# tec_controller.net
KiCad netlist of a schematic drawn in EAGLE
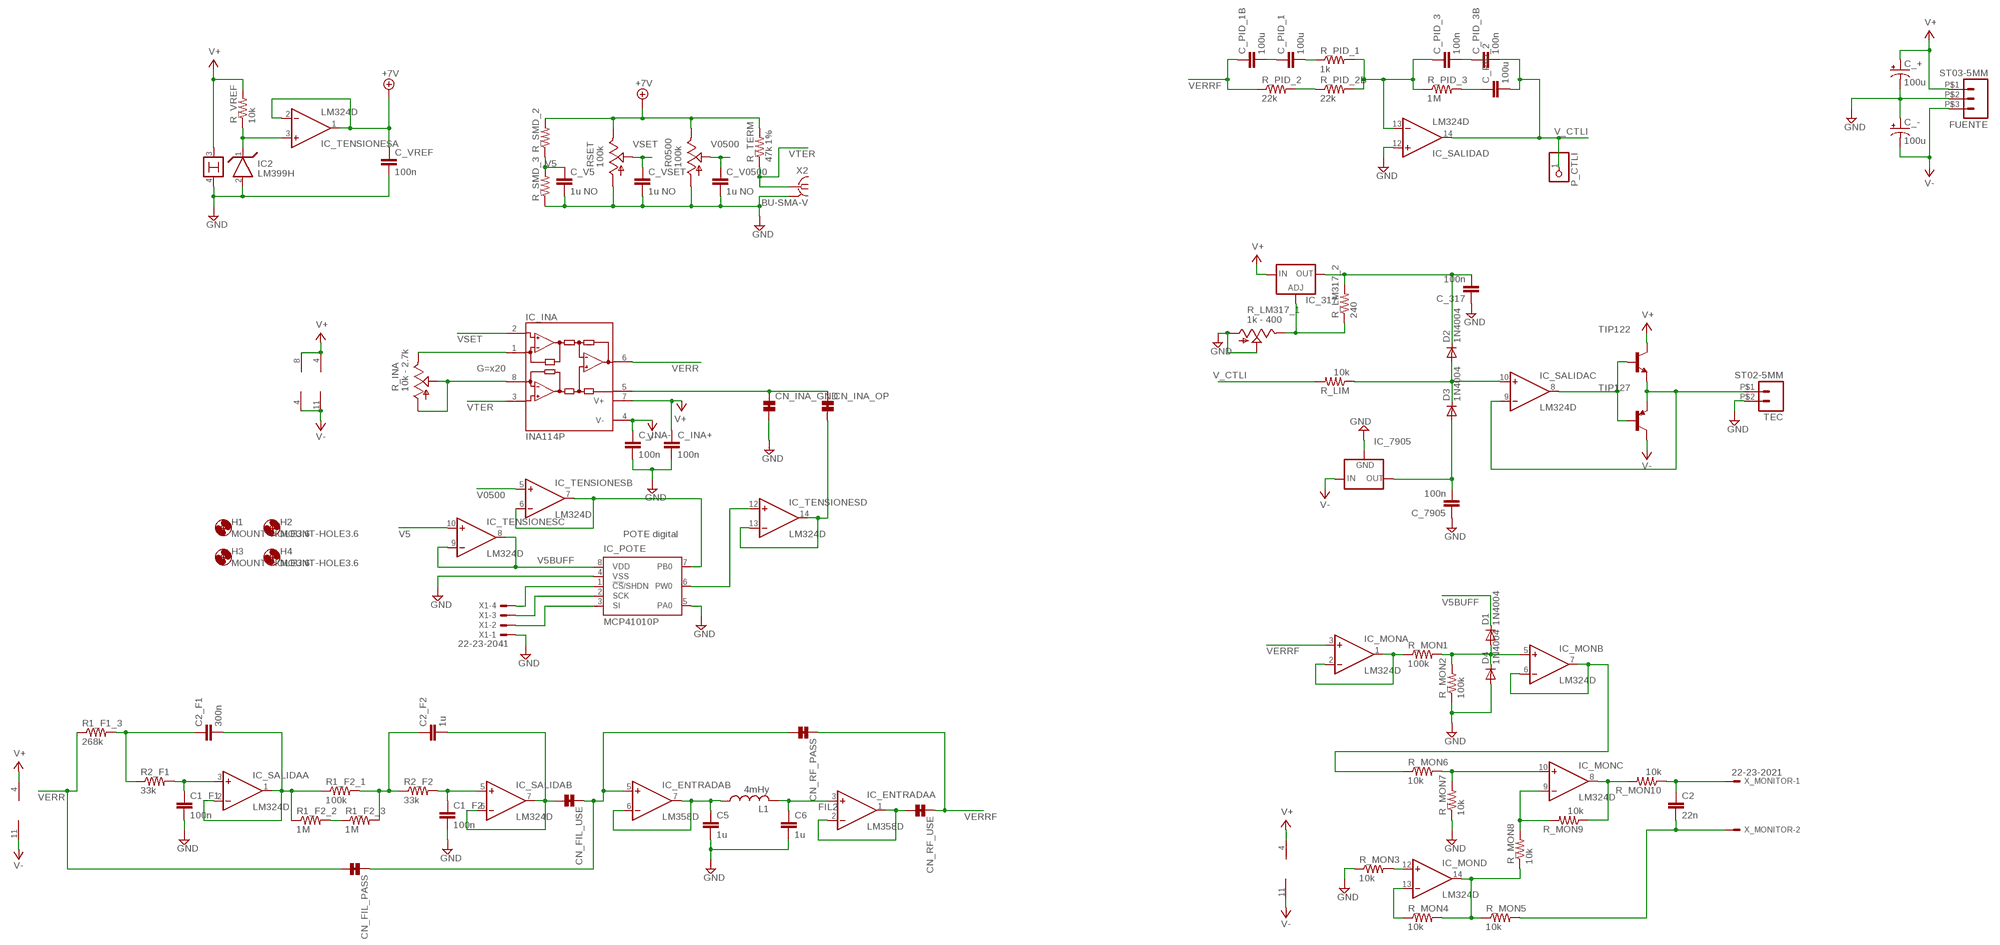
[diagram p0: schematic, sheet 1]

(export (version "E")
  (design (tool "Eeschema 10.0.6"))
  (components
    (comp (ref "C1_F1")
      (value "100n")
      (footprint "eagle-import:C0603")
      (libsource (lib "eagle-import") (part "C-EUC0603"))
    )
    (comp (ref "C1_F2")
      (value "100n")
      (footprint "eagle-import:C0603")
      (libsource (lib "eagle-import") (part "C-EUC0603"))
    )
    (comp (ref "C2")
      (value "22n")
      (footprint "eagle-import:C1206")
      (libsource (lib "eagle-import") (part "C-EUC1206"))
    )
    (comp (ref "C2_F1")
      (value "300n")
      (footprint "eagle-import:C0603")
      (libsource (lib "eagle-import") (part "C-EUC0603"))
    )
    (comp (ref "C2_F2")
      (value "1u")
      (footprint "eagle-import:C0805")
      (libsource (lib "eagle-import") (part "C-EUC0805"))
    )
    (comp (ref "C5")
      (value "1u")
      (footprint "eagle-import:C0805")
      (libsource (lib "eagle-import") (part "C-EUC0805"))
    )
    (comp (ref "C6")
      (value "1u")
      (footprint "eagle-import:C0805")
      (libsource (lib "eagle-import") (part "C-EUC0805"))
    )
    (comp (ref "CN_FIL_PASS")
      (value "LINK")
      (footprint "eagle-import:LINK_PAC_0603")
      (libsource (lib "eagle-import") (part "LINK"))
    )
    (comp (ref "CN_FIL_USE")
      (value "LINK")
      (footprint "eagle-import:LINK_PAC_0603")
      (libsource (lib "eagle-import") (part "LINK"))
    )
    (comp (ref "CN_INA_GND")
      (value "LINK")
      (footprint "eagle-import:LINK_PAC_0603")
      (libsource (lib "eagle-import") (part "LINK"))
    )
    (comp (ref "CN_INA_OP")
      (value "LINK")
      (footprint "eagle-import:LINK_PAC_0603")
      (libsource (lib "eagle-import") (part "LINK"))
    )
    (comp (ref "CN_RF_PASS")
      (value "LINK")
      (footprint "eagle-import:LINK_PAC_0603")
      (libsource (lib "eagle-import") (part "LINK"))
    )
    (comp (ref "CN_RF_USE")
      (value "LINK")
      (footprint "eagle-import:LINK_PAC_0603")
      (libsource (lib "eagle-import") (part "LINK"))
    )
    (comp (ref "C_+")
      (value "100u")
      (footprint "eagle-import:E3,5-10")
      (libsource (lib "eagle-import") (part "CPOL-USE3.5-10"))
    )
    (comp (ref "C_-")
      (value "100u")
      (footprint "eagle-import:E3,5-10")
      (libsource (lib "eagle-import") (part "CPOL-USE3.5-10"))
    )
    (comp (ref "C_317")
      (value "100n")
      (footprint "eagle-import:C0603")
      (libsource (lib "eagle-import") (part "C-EUC0603"))
    )
    (comp (ref "C_7905")
      (value "100n")
      (footprint "eagle-import:C0603")
      (libsource (lib "eagle-import") (part "C-EUC0603"))
    )
    (comp (ref "C_INA+")
      (value "100n")
      (footprint "eagle-import:C0603")
      (libsource (lib "eagle-import") (part "C-EUC0603"))
    )
    (comp (ref "C_INA-")
      (value "100n")
      (footprint "eagle-import:C0603")
      (libsource (lib "eagle-import") (part "C-EUC0603"))
    )
    (comp (ref "C_PID_1")
      (value "100u")
      (footprint "eagle-import:C050-050X075")
      (libsource (lib "eagle-import") (part "C-EU050-050X075"))
    )
    (comp (ref "C_PID_1B")
      (value "100u")
      (footprint "eagle-import:C050-050X075")
      (libsource (lib "eagle-import") (part "C-EU050-050X075"))
    )
    (comp (ref "C_PID_2")
      (value "100u")
      (footprint "eagle-import:C050-050X075")
      (libsource (lib "eagle-import") (part "C-EU050-050X075"))
    )
    (comp (ref "C_PID_3")
      (value "100n")
      (footprint "eagle-import:C0603")
      (libsource (lib "eagle-import") (part "C-EUC0603"))
    )
    (comp (ref "C_PID_3B")
      (value "100n")
      (footprint "eagle-import:C0603")
      (libsource (lib "eagle-import") (part "C-EUC0603"))
    )
    (comp (ref "C_V5")
      (value "1u NO")
      (footprint "eagle-import:C0805")
      (libsource (lib "eagle-import") (part "C-EUC0805"))
    )
    (comp (ref "C_V0500")
      (value "1u NO")
      (footprint "eagle-import:C0805")
      (libsource (lib "eagle-import") (part "C-EUC0805"))
    )
    (comp (ref "C_VREF")
      (value "100n")
      (footprint "eagle-import:C0603")
      (libsource (lib "eagle-import") (part "C-EUC0603"))
    )
    (comp (ref "C_VSET")
      (value "1u NO")
      (footprint "eagle-import:C0805")
      (libsource (lib "eagle-import") (part "C-EUC0805"))
    )
    (comp (ref "D1")
      (value "1N4004")
      (footprint "eagle-import:DO41-10")
      (libsource (lib "eagle-import") (part "1N4004"))
    )
    (comp (ref "D2")
      (value "1N4004")
      (footprint "eagle-import:DO41-10")
      (libsource (lib "eagle-import") (part "1N4004"))
    )
    (comp (ref "D3")
      (value "1N4004")
      (footprint "eagle-import:DO41-10")
      (libsource (lib "eagle-import") (part "1N4004"))
    )
    (comp (ref "D4")
      (value "1N4004")
      (footprint "eagle-import:DO41-10")
      (libsource (lib "eagle-import") (part "1N4004"))
    )
    (comp (ref "FUENTE")
      (value "ST03-5MM")
      (footprint "eagle-import:EK500V-03P")
      (libsource (lib "eagle-import") (part "ST03-5MM"))
    )
    (comp (ref "H1")
      (value "MOUNT-HOLE3.6")
      (footprint "eagle-import:3,6")
      (libsource (lib "eagle-import") (part "MOUNT-HOLE3.6"))
    )
    (comp (ref "H2")
      (value "MOUNT-HOLE3.6")
      (footprint "eagle-import:3,6")
      (libsource (lib "eagle-import") (part "MOUNT-HOLE3.6"))
    )
    (comp (ref "H3")
      (value "MOUNT-HOLE3.6")
      (footprint "eagle-import:3,6")
      (libsource (lib "eagle-import") (part "MOUNT-HOLE3.6"))
    )
    (comp (ref "H4")
      (value "MOUNT-HOLE3.6")
      (footprint "eagle-import:3,6")
      (libsource (lib "eagle-import") (part "MOUNT-HOLE3.6"))
    )
    (comp (ref "IC2")
      (value "LM399H")
      (footprint "eagle-import:TO39_4")
      (libsource (lib "eagle-import") (part "LM399H"))
    )
    (comp (ref "IC_317")
      (value "LM317TS")
      (footprint "eagle-import:317TS")
      (libsource (lib "eagle-import") (part "LM317TS"))
    )
    (comp (ref "IC_7905")
      (value "79XXS")
      (footprint "eagle-import:79XXS")
      (libsource (lib "eagle-import") (part "79XXS"))
    )
    (comp (ref "IC_ENTRADA")
      (value "LM358D")
      (footprint "eagle-import:SO08")
      (libsource (lib "eagle-import") (part "LM358D"))
    )
    (comp (ref "IC_INA")
      (value "INA114P")
      (footprint "eagle-import:DIL08")
      (fields (field (name "MF") "TEXAS INSTRUMENTS") (field (name "MPN") "INA114BP"))
      (libsource (lib "eagle-import") (part "INA114P"))
    )
    (comp (ref "IC_MON")
      (value "LM324D")
      (footprint "eagle-import:SO14")
      (libsource (lib "eagle-import") (part "LM324D"))
    )
    (comp (ref "IC_POTE")
      (value "MCP41010P")
      (footprint "eagle-import:DIL8")
      (fields (field (name "MF") "MICROCHIP"))
      (libsource (lib "eagle-import") (part "MCP41010P"))
    )
    (comp (ref "IC_SALIDA")
      (value "LM324D")
      (footprint "eagle-import:SO14")
      (libsource (lib "eagle-import") (part "LM324D"))
    )
    (comp (ref "IC_TENSIONES")
      (value "LM324D")
      (footprint "eagle-import:SO14")
      (libsource (lib "eagle-import") (part "LM324D"))
    )
    (comp (ref "L1")
      (value "4mHy")
      (footprint "eagle-import:0207_15")
      (libsource (lib "eagle-import") (part "L-US0207/15"))
    )
    (comp (ref "P_CTLI")
      (value "PINHD-1X1")
      (footprint "eagle-import:1X01")
      (libsource (lib "eagle-import") (part "PINHD-1X1"))
    )
    (comp (ref "R1_F1_3")
      (value "268k")
      (footprint "eagle-import:0207_15")
      (libsource (lib "eagle-import") (part "R-US_0207/15"))
    )
    (comp (ref "R1_F2_1")
      (value "100k")
      (footprint "eagle-import:M1206")
      (libsource (lib "eagle-import") (part "R-US_M1206"))
    )
    (comp (ref "R1_F2_2")
      (value "1M")
      (footprint "eagle-import:M1206")
      (libsource (lib "eagle-import") (part "R-US_M1206"))
    )
    (comp (ref "R1_F2_3")
      (value "1M")
      (footprint "eagle-import:M1206")
      (libsource (lib "eagle-import") (part "R-US_M1206"))
    )
    (comp (ref "R2_F1")
      (value "33k")
      (footprint "eagle-import:M1206")
      (libsource (lib "eagle-import") (part "R-US_M1206"))
    )
    (comp (ref "R2_F2")
      (value "33k")
      (footprint "eagle-import:M1206")
      (libsource (lib "eagle-import") (part "R-US_M1206"))
    )
    (comp (ref "R0500")
      (value "100k")
      (footprint "eagle-import:B64Y")
      (libsource (lib "eagle-import") (part "TRIM_US-B64Y"))
    )
    (comp (ref "RSET")
      (value "100k")
      (footprint "eagle-import:B64Y")
      (libsource (lib "eagle-import") (part "TRIM_US-B64Y"))
    )
    (comp (ref "R_INA")
      (value "10k - 2.7k")
      (footprint "eagle-import:B64Y")
      (libsource (lib "eagle-import") (part "TRIM_US-B64Y"))
    )
    (comp (ref "R_LIM")
      (value "10k")
      (footprint "eagle-import:M1206")
      (libsource (lib "eagle-import") (part "R-US_M1206"))
    )
    (comp (ref "R_LM317_1")
      (value "1k - 400")
      (footprint "eagle-import:B64Y")
      (libsource (lib "eagle-import") (part "TRIM_US-B64Y"))
    )
    (comp (ref "R_LM317_2")
      (value "240")
      (footprint "eagle-import:0207_10")
      (libsource (lib "eagle-import") (part "R-US_0207/10"))
    )
    (comp (ref "R_MON1")
      (value "100k")
      (footprint "eagle-import:M1206")
      (libsource (lib "eagle-import") (part "R-US_M1206"))
    )
    (comp (ref "R_MON2")
      (value "100k")
      (footprint "eagle-import:M1206")
      (libsource (lib "eagle-import") (part "R-US_M1206"))
    )
    (comp (ref "R_MON3")
      (value "10k")
      (footprint "eagle-import:M1206")
      (libsource (lib "eagle-import") (part "R-US_M1206"))
    )
    (comp (ref "R_MON4")
      (value "10k")
      (footprint "eagle-import:M1206")
      (libsource (lib "eagle-import") (part "R-US_M1206"))
    )
    (comp (ref "R_MON5")
      (value "10k")
      (footprint "eagle-import:M1206")
      (libsource (lib "eagle-import") (part "R-US_M1206"))
    )
    (comp (ref "R_MON6")
      (value "10k")
      (footprint "eagle-import:M1206")
      (libsource (lib "eagle-import") (part "R-US_M1206"))
    )
    (comp (ref "R_MON7")
      (value "10k")
      (footprint "eagle-import:M1206")
      (libsource (lib "eagle-import") (part "R-US_M1206"))
    )
    (comp (ref "R_MON8")
      (value "10k")
      (footprint "eagle-import:M1206")
      (libsource (lib "eagle-import") (part "R-US_M1206"))
    )
    (comp (ref "R_MON9")
      (value "10k")
      (footprint "eagle-import:M1206")
      (libsource (lib "eagle-import") (part "R-US_M1206"))
    )
    (comp (ref "R_MON10")
      (value "10k")
      (footprint "eagle-import:M1206")
      (libsource (lib "eagle-import") (part "R-US_M1206"))
    )
    (comp (ref "R_PID_1")
      (value "1k")
      (footprint "eagle-import:M1206")
      (libsource (lib "eagle-import") (part "R-US_M1206"))
    )
    (comp (ref "R_PID_2")
      (value "22k")
      (footprint "eagle-import:M1206")
      (libsource (lib "eagle-import") (part "R-US_M1206"))
    )
    (comp (ref "R_PID_2B")
      (value "22k")
      (footprint "eagle-import:M1206")
      (libsource (lib "eagle-import") (part "R-US_M1206"))
    )
    (comp (ref "R_PID_3")
      (value "1M")
      (footprint "eagle-import:M1206")
      (libsource (lib "eagle-import") (part "R-US_M1206"))
    )
    (comp (ref "R_SMD_2")
      (value "R-US_M1206")
      (footprint "eagle-import:M1206")
      (libsource (lib "eagle-import") (part "R-US_M1206"))
    )
    (comp (ref "R_SMD_3")
      (value "R-US_M1206")
      (footprint "eagle-import:M1206")
      (libsource (lib "eagle-import") (part "R-US_M1206"))
    )
    (comp (ref "R_TERM")
      (value "47k 1%")
      (footprint "eagle-import:0207_10")
      (libsource (lib "eagle-import") (part "R-US_0207/10"))
    )
    (comp (ref "R_VREF")
      (value "10k")
      (footprint "eagle-import:M1206")
      (libsource (lib "eagle-import") (part "R-US_M1206"))
    )
    (comp (ref "TEC")
      (value "ST02-5MM")
      (footprint "eagle-import:EK500V-02P")
      (libsource (lib "eagle-import") (part "ST02-5MM"))
    )
    (comp (ref "TIP122")
      (value "-NPN-TO126V")
      (footprint "eagle-import:TO126V")
      (libsource (lib "eagle-import") (part "-NPN-TO126V"))
    )
    (comp (ref "TIP127")
      (value "-PNP-TO126V")
      (footprint "eagle-import:TO126V")
      (libsource (lib "eagle-import") (part "-PNP-TO126V"))
    )
    (comp (ref "X1")
      (value "22-23-2041")
      (footprint "eagle-import:22-23-2041")
      (fields (field (name "MF") "MOLEX"))
      (libsource (lib "eagle-import") (part "22-23-2041"))
    )
    (comp (ref "X2")
      (value "BU-SMA-V")
      (footprint "eagle-import:BU-SMA-V")
      (libsource (lib "eagle-import") (part "BU-SMA-V"))
    )
    (comp (ref "X_MONITOR")
      (value "22-23-2021")
      (footprint "eagle-import:22-23-2021")
      (fields (field (name "MF") "MOLEX"))
      (libsource (lib "eagle-import") (part "22-23-2021"))
    )
  )
  (nets
    (net (code "1") (name "+7V") (class "Default")
      (node (ref "C_VREF") (pin "1") (pinfunction "1_1") (pintype "passive"))
      (node (ref "IC_TENSIONES") (pin "1") (pinfunction "OUT_1") (pintype "output"))
      (node (ref "IC_TENSIONES") (pin "2") (pinfunction "-IN_2") (pintype "input"))
      (node (ref "R0500") (pin "E") (pinfunction "E_E") (pintype "passive"))
      (node (ref "RSET") (pin "E") (pinfunction "E_E") (pintype "passive"))
      (node (ref "R_SMD_2") (pin "2") (pinfunction "2_2") (pintype "passive"))
      (node (ref "R_TERM") (pin "2") (pinfunction "2_2") (pintype "passive"))
    )
    (net (code "2") (name "/FIL2") (class "Default")
      (node (ref "C6") (pin "1") (pinfunction "1_1") (pintype "passive"))
      (node (ref "IC_ENTRADA") (pin "3") (pinfunction "+IN_3") (pintype "input"))
      (node (ref "L1") (pin "2") (pinfunction "2_2") (pintype "passive"))
    )
    (net (code "3") (name "/V5") (class "Default")
      (node (ref "C_V5") (pin "1") (pinfunction "1_1") (pintype "passive"))
      (node (ref "IC_TENSIONES") (pin "10") (pinfunction "+IN_10") (pintype "input"))
      (node (ref "R_SMD_2") (pin "1") (pinfunction "1_1") (pintype "passive"))
      (node (ref "R_SMD_3") (pin "2") (pinfunction "2_2") (pintype "passive"))
    )
    (net (code "4") (name "/V5BUFF") (class "Default")
      (node (ref "D1") (pin "C") (pinfunction "C_C") (pintype "passive"))
      (node (ref "IC_POTE") (pin "8") (pinfunction "VDD_8") (pintype "input"))
      (node (ref "IC_TENSIONES") (pin "8") (pinfunction "OUT_8") (pintype "output"))
      (node (ref "IC_TENSIONES") (pin "9") (pinfunction "-IN_9") (pintype "input"))
    )
    (net (code "5") (name "/V0500") (class "Default")
      (node (ref "C_V0500") (pin "1") (pinfunction "1_1") (pintype "passive"))
      (node (ref "IC_TENSIONES") (pin "5") (pinfunction "+IN_5") (pintype "input"))
      (node (ref "R0500") (pin "S") (pinfunction "S_S") (pintype "passive"))
    )
    (net (code "6") (name "/VERR") (class "Default")
      (node (ref "CN_FIL_PASS") (pin "2") (pinfunction "2_2") (pintype "passive"))
      (node (ref "IC_INA") (pin "6") (pinfunction "OUT_6") (pintype "output"))
      (node (ref "R1_F1_3") (pin "1") (pinfunction "1_1") (pintype "passive"))
    )
    (net (code "7") (name "/VERRF") (class "Default")
      (node (ref "CN_RF_PASS") (pin "1") (pinfunction "1_1") (pintype "passive"))
      (node (ref "CN_RF_USE") (pin "1") (pinfunction "1_1") (pintype "passive"))
      (node (ref "C_PID_1B") (pin "1") (pinfunction "1_1") (pintype "passive"))
      (node (ref "IC_MON") (pin "3") (pinfunction "+IN_3") (pintype "input"))
      (node (ref "R_PID_2") (pin "1") (pinfunction "1_1") (pintype "passive"))
    )
    (net (code "8") (name "/VSET") (class "Default")
      (node (ref "C_VSET") (pin "1") (pinfunction "1_1") (pintype "passive"))
      (node (ref "IC_INA") (pin "2") (pinfunction "-IN_2") (pintype "input"))
      (node (ref "RSET") (pin "S") (pinfunction "S_S") (pintype "passive"))
    )
    (net (code "9") (name "/VTER") (class "Default")
      (node (ref "IC_INA") (pin "3") (pinfunction "+IN_3") (pintype "input"))
      (node (ref "R_TERM") (pin "1") (pinfunction "1_1") (pintype "passive"))
      (node (ref "X2") (pin "1") (pinfunction "1_1") (pintype "passive"))
    )
    (net (code "10") (name "/V_CTLI") (class "Default")
      (node (ref "C_PID_2") (pin "2") (pinfunction "2_2") (pintype "passive"))
      (node (ref "C_PID_3B") (pin "2") (pinfunction "2_2") (pintype "passive"))
      (node (ref "IC_SALIDA") (pin "14") (pinfunction "OUT_14") (pintype "output"))
      (node (ref "P_CTLI") (pin "1") (pinfunction "1_1") (pintype "passive"))
      (node (ref "R_LIM") (pin "2") (pinfunction "2_2") (pintype "passive"))
    )
    (net (code "11") (name "GND") (class "Default")
      (node (ref "C1_F1") (pin "2") (pinfunction "2_2") (pintype "passive"))
      (node (ref "C1_F2") (pin "2") (pinfunction "2_2") (pintype "passive"))
      (node (ref "C5") (pin "2") (pinfunction "2_2") (pintype "passive"))
      (node (ref "C6") (pin "2") (pinfunction "2_2") (pintype "passive"))
      (node (ref "CN_INA_GND") (pin "2") (pinfunction "2_2") (pintype "passive"))
      (node (ref "C_+") (pin "-") (pinfunction "-_-") (pintype "passive"))
      (node (ref "C_-") (pin "+") (pinfunction "+_+") (pintype "passive"))
      (node (ref "C_317") (pin "1") (pinfunction "1_1") (pintype "passive"))
      (node (ref "C_7905") (pin "1") (pinfunction "1_1") (pintype "passive"))
      (node (ref "C_INA+") (pin "2") (pinfunction "2_2") (pintype "passive"))
      (node (ref "C_INA-") (pin "2") (pinfunction "2_2") (pintype "passive"))
      (node (ref "C_V0500") (pin "2") (pinfunction "2_2") (pintype "passive"))
      (node (ref "C_V5") (pin "2") (pinfunction "2_2") (pintype "passive"))
      (node (ref "C_VREF") (pin "2") (pinfunction "2_2") (pintype "passive"))
      (node (ref "C_VSET") (pin "2") (pinfunction "2_2") (pintype "passive"))
      (node (ref "D4") (pin "A") (pinfunction "A_A") (pintype "passive"))
      (node (ref "FUENTE") (pin "P$2") (pinfunction "2_P$2") (pintype "passive"))
      (node (ref "IC2") (pin "2") (pinfunction "2_2") (pintype "input"))
      (node (ref "IC2") (pin "4") (pinfunction "4_4") (pintype "input"))
      (node (ref "IC_7905") (pin "GND") (pinfunction "GND_GND") (pintype "input"))
      (node (ref "IC_POTE") (pin "4") (pinfunction "VSS_4") (pintype "input"))
      (node (ref "IC_POTE") (pin "5") (pinfunction "PA0_5") (pintype "input"))
      (node (ref "IC_SALIDA") (pin "12") (pinfunction "+IN_12") (pintype "input"))
      (node (ref "R0500") (pin "A") (pinfunction "A_A") (pintype "passive"))
      (node (ref "RSET") (pin "A") (pinfunction "A_A") (pintype "passive"))
      (node (ref "R_LM317_1") (pin "A") (pinfunction "A_A") (pintype "passive"))
      (node (ref "R_LM317_1") (pin "S") (pinfunction "S_S") (pintype "passive"))
      (node (ref "R_MON2") (pin "1") (pinfunction "1_1") (pintype "passive"))
      (node (ref "R_MON3") (pin "1") (pinfunction "1_1") (pintype "passive"))
      (node (ref "R_MON7") (pin "1") (pinfunction "1_1") (pintype "passive"))
      (node (ref "R_SMD_3") (pin "1") (pinfunction "1_1") (pintype "passive"))
      (node (ref "TEC") (pin "P$2") (pinfunction "2_P$2") (pintype "passive"))
      (node (ref "X1") (pin "1") (pinfunction "S_1") (pintype "passive"))
      (node (ref "X2") (pin "2") (pinfunction "2_2") (pintype "passive"))
      (node (ref "X2") (pin "3") (pinfunction "2_3") (pintype "passive"))
      (node (ref "X2") (pin "4") (pinfunction "2_4") (pintype "passive"))
      (node (ref "X2") (pin "5") (pinfunction "2_5") (pintype "passive"))
    )
    (net (code "12") (name "Net-(C2_F1-Pad1)") (class "Default")
      (node (ref "C2_F1") (pin "1") (pinfunction "1_1") (pintype "passive"))
      (node (ref "R1_F1_3") (pin "2") (pinfunction "2_2") (pintype "passive"))
      (node (ref "R2_F1") (pin "1") (pinfunction "1_1") (pintype "passive"))
    )
    (net (code "13") (name "Net-(C2_F2-Pad1)") (class "Default")
      (node (ref "C2_F2") (pin "1") (pinfunction "1_1") (pintype "passive"))
      (node (ref "R1_F2_1") (pin "2") (pinfunction "2_2") (pintype "passive"))
      (node (ref "R1_F2_3") (pin "2") (pinfunction "2_2") (pintype "passive"))
      (node (ref "R2_F2") (pin "1") (pinfunction "1_1") (pintype "passive"))
    )
    (net (code "14") (name "Net-(C_7905-Pad2)") (class "Default")
      (node (ref "C_7905") (pin "2") (pinfunction "2_2") (pintype "passive"))
      (node (ref "D3") (pin "A") (pinfunction "A_A") (pintype "passive"))
      (node (ref "IC_7905") (pin "OUT") (pinfunction "OUT_OUT") (pintype "passive"))
    )
    (net (code "15") (name "Net-(C_PID_1-Pad1)") (class "Default")
      (node (ref "C_PID_1") (pin "1") (pinfunction "1_1") (pintype "passive"))
      (node (ref "C_PID_1B") (pin "2") (pinfunction "2_2") (pintype "passive"))
    )
    (net (code "16") (name "Net-(C_PID_1-Pad2)") (class "Default")
      (node (ref "C_PID_1") (pin "2") (pinfunction "2_2") (pintype "passive"))
      (node (ref "R_PID_1") (pin "1") (pinfunction "1_1") (pintype "passive"))
    )
    (net (code "17") (name "Net-(C_PID_2-Pad1)") (class "Default")
      (node (ref "C_PID_2") (pin "1") (pinfunction "1_1") (pintype "passive"))
      (node (ref "R_PID_3") (pin "2") (pinfunction "2_2") (pintype "passive"))
    )
    (net (code "18") (name "Net-(C_PID_3-Pad2)") (class "Default")
      (node (ref "C_PID_3") (pin "2") (pinfunction "2_2") (pintype "passive"))
      (node (ref "C_PID_3B") (pin "1") (pinfunction "1_1") (pintype "passive"))
    )
    (net (code "19") (name "Net-(IC_317-ADJ)") (class "Default")
      (node (ref "IC_317") (pin "1") (pinfunction "ADJ_1") (pintype "input"))
      (node (ref "R_LM317_1") (pin "E") (pinfunction "E_E") (pintype "passive"))
      (node (ref "R_LM317_2") (pin "1") (pinfunction "1_1") (pintype "passive"))
    )
    (net (code "20") (name "Net-(IC_317-OUT)") (class "Default")
      (node (ref "C_317") (pin "2") (pinfunction "2_2") (pintype "passive"))
      (node (ref "D2") (pin "C") (pinfunction "C_C") (pintype "passive"))
      (node (ref "IC_317") (pin "2") (pinfunction "OUT_2") (pintype "passive"))
      (node (ref "R_LM317_2") (pin "2") (pinfunction "2_2") (pintype "passive"))
    )
    (net (code "21") (name "Net-(IC_ENTRADAA--IN)") (class "Default")
      (node (ref "CN_RF_USE") (pin "2") (pinfunction "2_2") (pintype "passive"))
      (node (ref "IC_ENTRADA") (pin "1") (pinfunction "OUT_1") (pintype "output"))
      (node (ref "IC_ENTRADA") (pin "2") (pinfunction "-IN_2") (pintype "input"))
    )
    (net (code "22") (name "Net-(IC_ENTRADAB-+IN)") (class "Default")
      (node (ref "CN_FIL_PASS") (pin "1") (pinfunction "1_1") (pintype "passive"))
      (node (ref "CN_FIL_USE") (pin "1") (pinfunction "1_1") (pintype "passive"))
      (node (ref "CN_RF_PASS") (pin "2") (pinfunction "2_2") (pintype "passive"))
      (node (ref "IC_ENTRADA") (pin "5") (pinfunction "+IN_5") (pintype "input"))
    )
    (net (code "23") (name "Net-(IC_ENTRADAB--IN)") (class "Default")
      (node (ref "C5") (pin "1") (pinfunction "1_1") (pintype "passive"))
      (node (ref "IC_ENTRADA") (pin "6") (pinfunction "-IN_6") (pintype "input"))
      (node (ref "IC_ENTRADA") (pin "7") (pinfunction "OUT_7") (pintype "output"))
      (node (ref "L1") (pin "1") (pinfunction "1_1") (pintype "passive"))
    )
    (net (code "24") (name "Net-(IC_INA-REF)") (class "Default")
      (node (ref "CN_INA_GND") (pin "1") (pinfunction "1_1") (pintype "passive"))
      (node (ref "CN_INA_OP") (pin "1") (pinfunction "1_1") (pintype "passive"))
      (node (ref "IC_INA") (pin "5") (pinfunction "REF_5") (pintype "passive"))
    )
    (net (code "25") (name "Net-(IC_INA-RG-Pad1)") (class "Default")
      (node (ref "IC_INA") (pin "1") (pinfunction "RG_1") (pintype "passive"))
      (node (ref "R_INA") (pin "E") (pinfunction "E_E") (pintype "passive"))
    )
    (net (code "26") (name "Net-(IC_INA-RG-Pad8)") (class "Default")
      (node (ref "IC_INA") (pin "8") (pinfunction "RG_8") (pintype "passive"))
      (node (ref "R_INA") (pin "A") (pinfunction "A_A") (pintype "passive"))
      (node (ref "R_INA") (pin "S") (pinfunction "S_S") (pintype "passive"))
    )
    (net (code "27") (name "Net-(IC_MONA--IN)") (class "Default")
      (node (ref "IC_MON") (pin "1") (pinfunction "OUT_1") (pintype "output"))
      (node (ref "IC_MON") (pin "2") (pinfunction "-IN_2") (pintype "input"))
      (node (ref "R_MON1") (pin "1") (pinfunction "1_1") (pintype "passive"))
    )
    (net (code "28") (name "Net-(IC_MONB-+IN)") (class "Default")
      (node (ref "D1") (pin "A") (pinfunction "A_A") (pintype "passive"))
      (node (ref "D4") (pin "C") (pinfunction "C_C") (pintype "passive"))
      (node (ref "IC_MON") (pin "5") (pinfunction "+IN_5") (pintype "input"))
      (node (ref "R_MON1") (pin "2") (pinfunction "2_2") (pintype "passive"))
      (node (ref "R_MON2") (pin "2") (pinfunction "2_2") (pintype "passive"))
    )
    (net (code "29") (name "Net-(IC_MONB--IN)") (class "Default")
      (node (ref "IC_MON") (pin "6") (pinfunction "-IN_6") (pintype "input"))
      (node (ref "IC_MON") (pin "7") (pinfunction "OUT_7") (pintype "output"))
      (node (ref "R_MON6") (pin "1") (pinfunction "1_1") (pintype "passive"))
    )
    (net (code "30") (name "Net-(IC_MONC-+IN)") (class "Default")
      (node (ref "IC_MON") (pin "10") (pinfunction "+IN_10") (pintype "input"))
      (node (ref "R_MON6") (pin "2") (pinfunction "2_2") (pintype "passive"))
      (node (ref "R_MON7") (pin "2") (pinfunction "2_2") (pintype "passive"))
    )
    (net (code "31") (name "Net-(IC_MONC--IN)") (class "Default")
      (node (ref "IC_MON") (pin "9") (pinfunction "-IN_9") (pintype "input"))
      (node (ref "R_MON8") (pin "2") (pinfunction "2_2") (pintype "passive"))
      (node (ref "R_MON9") (pin "2") (pinfunction "2_2") (pintype "passive"))
    )
    (net (code "32") (name "Net-(IC_MONC-OUT)") (class "Default")
      (node (ref "IC_MON") (pin "8") (pinfunction "OUT_8") (pintype "output"))
      (node (ref "R_MON10") (pin "2") (pinfunction "2_2") (pintype "passive"))
      (node (ref "R_MON9") (pin "1") (pinfunction "1_1") (pintype "passive"))
    )
    (net (code "33") (name "Net-(IC_MOND-+IN)") (class "Default")
      (node (ref "IC_MON") (pin "12") (pinfunction "+IN_12") (pintype "input"))
      (node (ref "R_MON3") (pin "2") (pinfunction "2_2") (pintype "passive"))
    )
    (net (code "34") (name "Net-(IC_MOND--IN)") (class "Default")
      (node (ref "IC_MON") (pin "13") (pinfunction "-IN_13") (pintype "input"))
      (node (ref "R_MON4") (pin "1") (pinfunction "1_1") (pintype "passive"))
    )
    (net (code "35") (name "Net-(IC_MOND-OUT)") (class "Default")
      (node (ref "IC_MON") (pin "14") (pinfunction "OUT_14") (pintype "output"))
      (node (ref "R_MON4") (pin "2") (pinfunction "2_2") (pintype "passive"))
      (node (ref "R_MON5") (pin "1") (pinfunction "1_1") (pintype "passive"))
      (node (ref "R_MON8") (pin "1") (pinfunction "1_1") (pintype "passive"))
    )
    (net (code "36") (name "Net-(IC_POTE-PB0)") (class "Default")
      (node (ref "IC_POTE") (pin "7") (pinfunction "PB0_7") (pintype "input"))
      (node (ref "IC_TENSIONES") (pin "6") (pinfunction "-IN_6") (pintype "input"))
      (node (ref "IC_TENSIONES") (pin "7") (pinfunction "OUT_7") (pintype "output"))
    )
    (net (code "37") (name "Net-(IC_POTE-PW0)") (class "Default")
      (node (ref "IC_POTE") (pin "6") (pinfunction "PW0_6") (pintype "input"))
      (node (ref "IC_TENSIONES") (pin "12") (pinfunction "+IN_12") (pintype "input"))
    )
    (net (code "38") (name "Net-(IC_POTE-SCK)") (class "Default")
      (node (ref "IC_POTE") (pin "2") (pinfunction "SCK_2") (pintype "input"))
      (node (ref "X1") (pin "3") (pinfunction "S_3") (pintype "passive"))
    )
    (net (code "39") (name "Net-(IC_POTE-SI)") (class "Default")
      (node (ref "IC_POTE") (pin "3") (pinfunction "SI_3") (pintype "input"))
      (node (ref "X1") (pin "2") (pinfunction "S_2") (pintype "passive"))
    )
    (net (code "40") (name "Net-(IC_POTE-~{CS}{slash}SHDN)") (class "Default")
      (node (ref "IC_POTE") (pin "1") (pinfunction "~{CS}/SHDN_1") (pintype "input"))
      (node (ref "X1") (pin "4") (pinfunction "S_4") (pintype "passive"))
    )
    (net (code "41") (name "Net-(IC_SALIDAA-+IN)") (class "Default")
      (node (ref "C1_F1") (pin "1") (pinfunction "1_1") (pintype "passive"))
      (node (ref "IC_SALIDA") (pin "3") (pinfunction "+IN_3") (pintype "input"))
      (node (ref "R2_F1") (pin "2") (pinfunction "2_2") (pintype "passive"))
    )
    (net (code "42") (name "Net-(IC_SALIDAA--IN)") (class "Default")
      (node (ref "C2_F1") (pin "2") (pinfunction "2_2") (pintype "passive"))
      (node (ref "IC_SALIDA") (pin "1") (pinfunction "OUT_1") (pintype "output"))
      (node (ref "IC_SALIDA") (pin "2") (pinfunction "-IN_2") (pintype "input"))
      (node (ref "R1_F2_1") (pin "1") (pinfunction "1_1") (pintype "passive"))
      (node (ref "R1_F2_2") (pin "1") (pinfunction "1_1") (pintype "passive"))
    )
    (net (code "43") (name "Net-(IC_SALIDAB-+IN)") (class "Default")
      (node (ref "C1_F2") (pin "1") (pinfunction "1_1") (pintype "passive"))
      (node (ref "IC_SALIDA") (pin "5") (pinfunction "+IN_5") (pintype "input"))
      (node (ref "R2_F2") (pin "2") (pinfunction "2_2") (pintype "passive"))
    )
    (net (code "44") (name "Net-(IC_SALIDAB--IN)") (class "Default")
      (node (ref "C2_F2") (pin "2") (pinfunction "2_2") (pintype "passive"))
      (node (ref "CN_FIL_USE") (pin "2") (pinfunction "2_2") (pintype "passive"))
      (node (ref "IC_SALIDA") (pin "6") (pinfunction "-IN_6") (pintype "input"))
      (node (ref "IC_SALIDA") (pin "7") (pinfunction "OUT_7") (pintype "output"))
    )
    (net (code "45") (name "Net-(IC_SALIDAC-+IN)") (class "Default")
      (node (ref "D2") (pin "A") (pinfunction "A_A") (pintype "passive"))
      (node (ref "D3") (pin "C") (pinfunction "C_C") (pintype "passive"))
      (node (ref "IC_SALIDA") (pin "10") (pinfunction "+IN_10") (pintype "input"))
      (node (ref "R_LIM") (pin "1") (pinfunction "1_1") (pintype "passive"))
    )
    (net (code "46") (name "Net-(IC_SALIDAC--IN)") (class "Default")
      (node (ref "IC_SALIDA") (pin "9") (pinfunction "-IN_9") (pintype "input"))
      (node (ref "TEC") (pin "P$1") (pinfunction "1_P$1") (pintype "passive"))
      (node (ref "TIP122") (pin "1") (pinfunction "E_1") (pintype "passive"))
      (node (ref "TIP127") (pin "1") (pinfunction "E_1") (pintype "passive"))
    )
    (net (code "47") (name "Net-(IC_SALIDAC-OUT)") (class "Default")
      (node (ref "IC_SALIDA") (pin "8") (pinfunction "OUT_8") (pintype "output"))
      (node (ref "TIP122") (pin "3") (pinfunction "B_3") (pintype "passive"))
      (node (ref "TIP127") (pin "3") (pinfunction "B_3") (pintype "passive"))
    )
    (net (code "48") (name "Net-(IC_SALIDAD--IN)") (class "Default")
      (node (ref "C_PID_3") (pin "1") (pinfunction "1_1") (pintype "passive"))
      (node (ref "IC_SALIDA") (pin "13") (pinfunction "-IN_13") (pintype "input"))
      (node (ref "R_PID_1") (pin "2") (pinfunction "2_2") (pintype "passive"))
      (node (ref "R_PID_2B") (pin "2") (pinfunction "2_2") (pintype "passive"))
      (node (ref "R_PID_3") (pin "1") (pinfunction "1_1") (pintype "passive"))
    )
    (net (code "49") (name "Net-(IC_TENSIONESA-+IN)") (class "Default")
      (node (ref "IC2") (pin "1") (pinfunction "1_1") (pintype "input"))
      (node (ref "IC_TENSIONES") (pin "3") (pinfunction "+IN_3") (pintype "input"))
      (node (ref "R_VREF") (pin "1") (pinfunction "1_1") (pintype "passive"))
    )
    (net (code "50") (name "Net-(IC_TENSIONESD--IN)") (class "Default")
      (node (ref "CN_INA_OP") (pin "2") (pinfunction "2_2") (pintype "passive"))
      (node (ref "IC_TENSIONES") (pin "13") (pinfunction "-IN_13") (pintype "input"))
      (node (ref "IC_TENSIONES") (pin "14") (pinfunction "OUT_14") (pintype "output"))
    )
    (net (code "51") (name "Net-(R1_F2_2-Pad2)") (class "Default")
      (node (ref "R1_F2_2") (pin "2") (pinfunction "2_2") (pintype "passive"))
      (node (ref "R1_F2_3") (pin "1") (pinfunction "1_1") (pintype "passive"))
    )
    (net (code "52") (name "Net-(R_PID_2-Pad2)") (class "Default")
      (node (ref "R_PID_2") (pin "2") (pinfunction "2_2") (pintype "passive"))
      (node (ref "R_PID_2B") (pin "1") (pinfunction "1_1") (pintype "passive"))
    )
    (net (code "53") (name "Net-(X_MONITORA-S)") (class "Default")
      (node (ref "C2") (pin "1") (pinfunction "1_1") (pintype "passive"))
      (node (ref "R_MON10") (pin "1") (pinfunction "1_1") (pintype "passive"))
      (node (ref "X_MONITOR") (pin "1") (pinfunction "S_1") (pintype "passive"))
    )
    (net (code "54") (name "Net-(X_MONITORB-S)") (class "Default")
      (node (ref "C2") (pin "2") (pinfunction "2_2") (pintype "passive"))
      (node (ref "R_MON5") (pin "2") (pinfunction "2_2") (pintype "passive"))
      (node (ref "X_MONITOR") (pin "2") (pinfunction "S_2") (pintype "passive"))
    )
    (net (code "55") (name "V+") (class "Default")
      (node (ref "C_+") (pin "+") (pinfunction "+_+") (pintype "passive"))
      (node (ref "C_INA+") (pin "1") (pinfunction "1_1") (pintype "passive"))
      (node (ref "FUENTE") (pin "P$1") (pinfunction "1_P$1") (pintype "passive"))
      (node (ref "IC2") (pin "3") (pinfunction "3_3") (pintype "input"))
      (node (ref "IC_317") (pin "3") (pinfunction "IN_3") (pintype "input"))
      (node (ref "IC_ENTRADA") (pin "8") (pinfunction "V+_8") (pintype "power_in"))
      (node (ref "IC_INA") (pin "7") (pinfunction "V+_7") (pintype "power_in"))
      (node (ref "IC_MON") (pin "4") (pinfunction "V+_4") (pintype "power_in"))
      (node (ref "IC_SALIDA") (pin "4") (pinfunction "V+_4") (pintype "power_in"))
      (node (ref "IC_TENSIONES") (pin "4") (pinfunction "V+_4") (pintype "power_in"))
      (node (ref "R_VREF") (pin "2") (pinfunction "2_2") (pintype "passive"))
      (node (ref "TIP122") (pin "2") (pinfunction "C_2") (pintype "passive"))
    )
    (net (code "56") (name "V-") (class "Default")
      (node (ref "C_-") (pin "-") (pinfunction "-_-") (pintype "passive"))
      (node (ref "C_INA-") (pin "1") (pinfunction "1_1") (pintype "passive"))
      (node (ref "FUENTE") (pin "P$3") (pinfunction "3_P$3") (pintype "passive"))
      (node (ref "IC_7905") (pin "IN") (pinfunction "IN_IN") (pintype "input"))
      (node (ref "IC_ENTRADA") (pin "4") (pinfunction "V-_4") (pintype "power_in"))
      (node (ref "IC_INA") (pin "4") (pinfunction "V-_4") (pintype "power_in"))
      (node (ref "IC_MON") (pin "11") (pinfunction "V-_11") (pintype "power_in"))
      (node (ref "IC_SALIDA") (pin "11") (pinfunction "V-_11") (pintype "power_in"))
      (node (ref "IC_TENSIONES") (pin "11") (pinfunction "V-_11") (pintype "power_in"))
      (node (ref "TIP127") (pin "2") (pinfunction "C_2") (pintype "passive"))
    )
  )
)
